# SWD.net
KiCad netlist of a schematic drawn in EAGLE
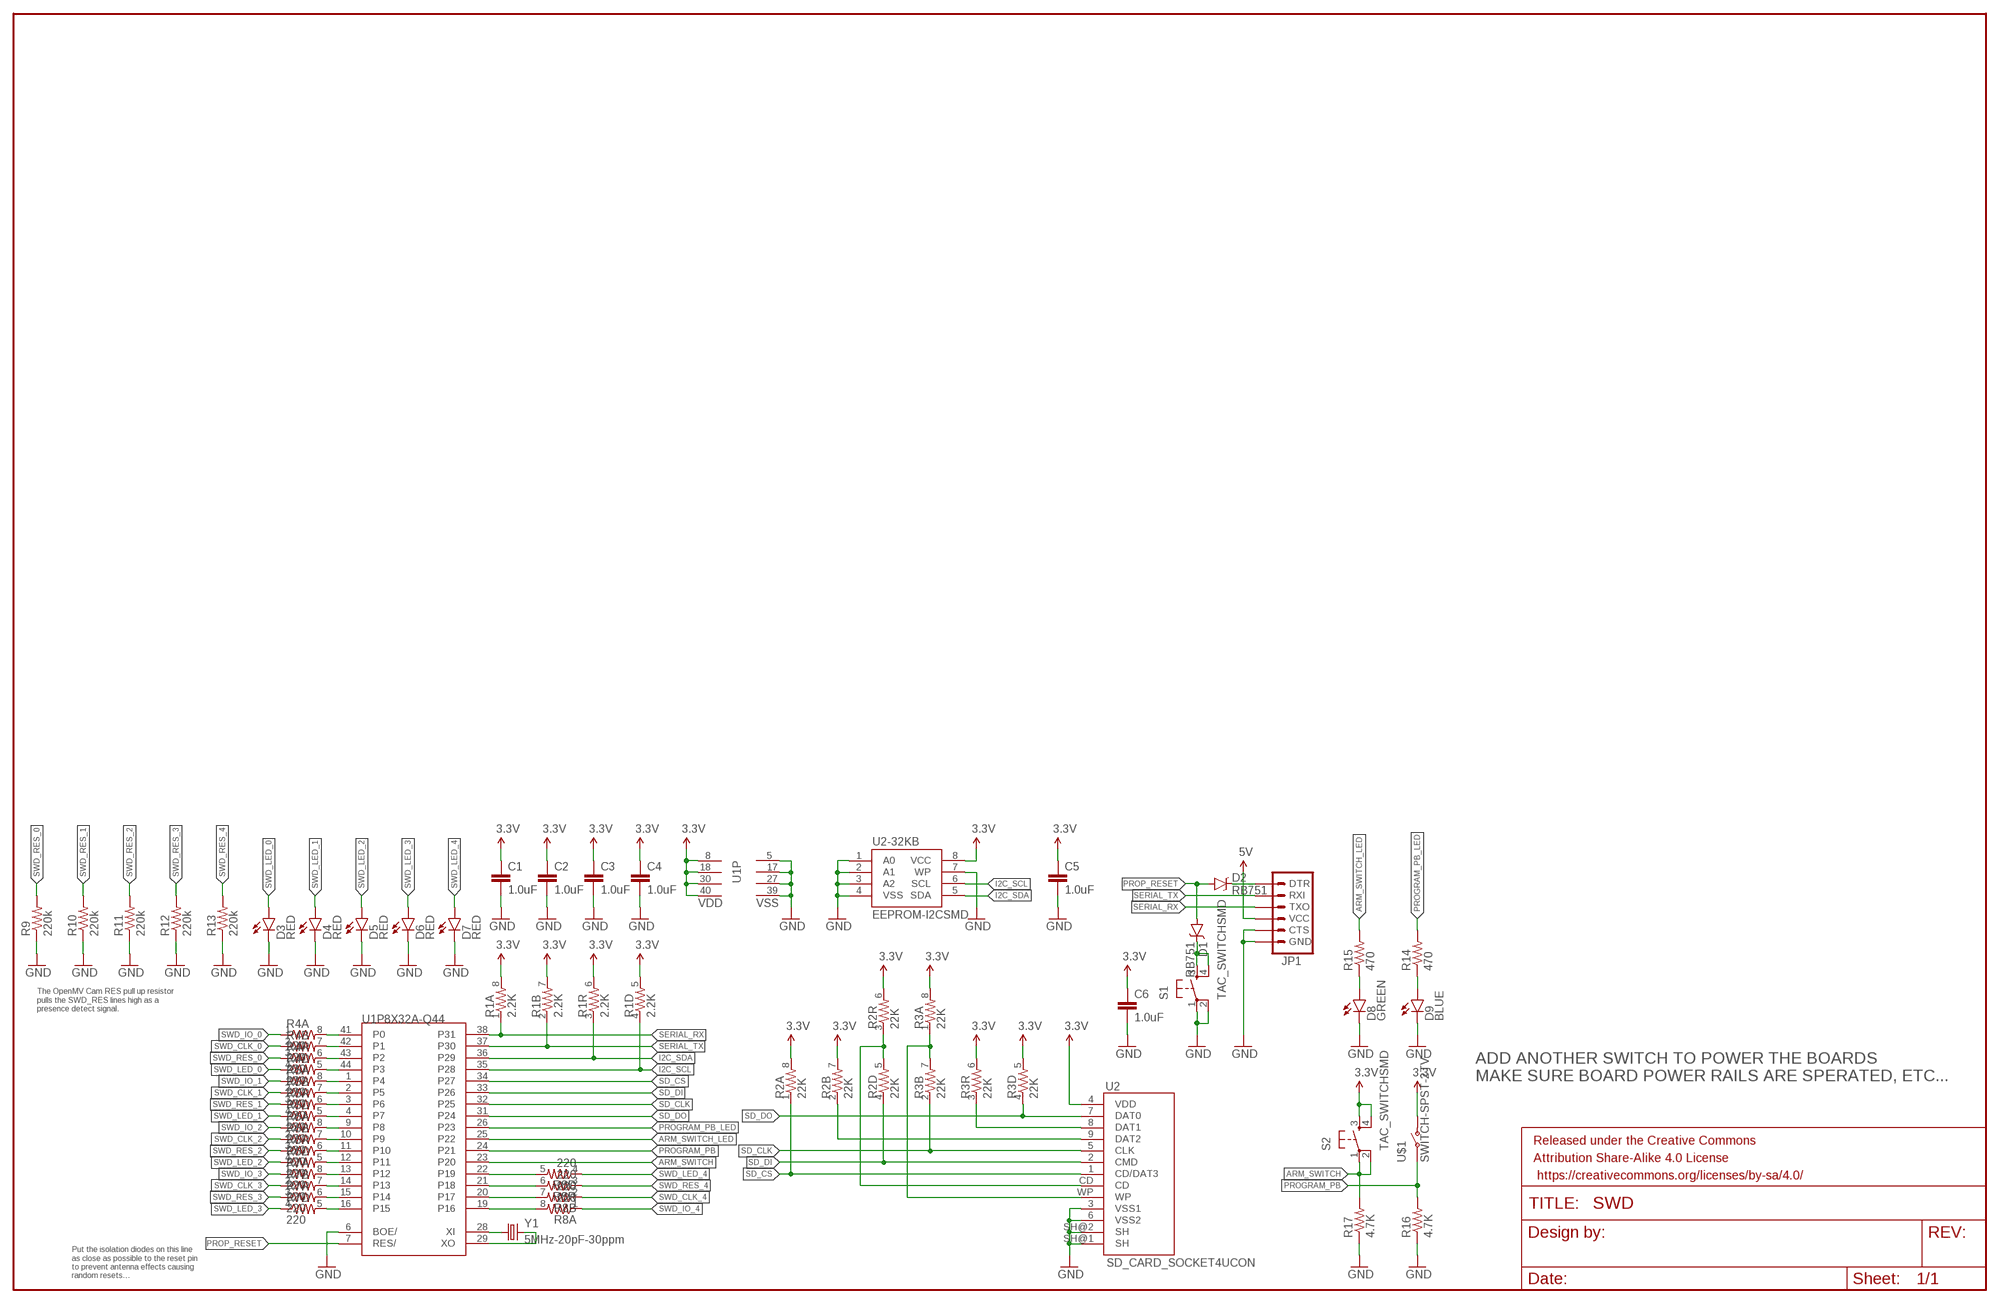
[diagram p0: schematic, sheet 1]

(export (version "E")
  (design (tool "Eeschema 10.0.6"))
  (components
    (comp (ref "C1")
      (value "1.0uF")
      (footprint "eagle-import:0402-CAP")
      (libsource (lib "eagle-import") (part "1.0UF-16V-10%(0402)"))
    )
    (comp (ref "C2")
      (value "1.0uF")
      (footprint "eagle-import:0402-CAP")
      (libsource (lib "eagle-import") (part "1.0UF-16V-10%(0402)"))
    )
    (comp (ref "C3")
      (value "1.0uF")
      (footprint "eagle-import:0402-CAP")
      (libsource (lib "eagle-import") (part "1.0UF-16V-10%(0402)"))
    )
    (comp (ref "C4")
      (value "1.0uF")
      (footprint "eagle-import:0402-CAP")
      (libsource (lib "eagle-import") (part "1.0UF-16V-10%(0402)"))
    )
    (comp (ref "C5")
      (value "1.0uF")
      (footprint "eagle-import:0402-CAP")
      (libsource (lib "eagle-import") (part "1.0UF-16V-10%(0402)"))
    )
    (comp (ref "C6")
      (value "1.0uF")
      (footprint "eagle-import:0402-CAP")
      (libsource (lib "eagle-import") (part "1.0UF-16V-10%(0402)"))
    )
    (comp (ref "D1")
      (value "RB751")
      (footprint "eagle-import:SOD-523")
      (libsource (lib "eagle-import") (part "RB751"))
    )
    (comp (ref "D2")
      (value "RB751")
      (footprint "eagle-import:SOD-523")
      (libsource (lib "eagle-import") (part "RB751"))
    )
    (comp (ref "D3")
      (value "RED")
      (footprint "eagle-import:LED-0603")
      (libsource (lib "eagle-import") (part "LED-RED0603"))
    )
    (comp (ref "D4")
      (value "RED")
      (footprint "eagle-import:LED-0603")
      (libsource (lib "eagle-import") (part "LED-RED0603"))
    )
    (comp (ref "D5")
      (value "RED")
      (footprint "eagle-import:LED-0603")
      (libsource (lib "eagle-import") (part "LED-RED0603"))
    )
    (comp (ref "D6")
      (value "RED")
      (footprint "eagle-import:LED-0603")
      (libsource (lib "eagle-import") (part "LED-RED0603"))
    )
    (comp (ref "D7")
      (value "RED")
      (footprint "eagle-import:LED-0603")
      (libsource (lib "eagle-import") (part "LED-RED0603"))
    )
    (comp (ref "D8")
      (value "GREEN")
      (footprint "eagle-import:LED-0603")
      (libsource (lib "eagle-import") (part "LED-GREEN0603"))
    )
    (comp (ref "D9")
      (value "BLUE")
      (footprint "eagle-import:LED-0603")
      (libsource (lib "eagle-import") (part "LED-BLUE0603"))
    )
    (comp (ref "FRAME1")
      (value "FRAME-LEDGER")
      (footprint "eagle-import:CREATIVE_COMMONS")
      (libsource (lib "eagle-import") (part "FRAME-LEDGER"))
    )
    (comp (ref "JP1")
      (value "ARDUINO_SERIAL_PROGRAMPTH")
      (footprint "eagle-import:1X06")
      (libsource (lib "eagle-import") (part "ARDUINO_SERIAL_PROGRAMPTH"))
    )
    (comp (ref "R1")
      (value "2.2K")
      (footprint "eagle-import:0603-ARV")
      (libsource (lib "eagle-import") (part "RESISTOR-ARRAY0603-ARV"))
    )
    (comp (ref "R2")
      (value "22K")
      (footprint "eagle-import:0603-ARV")
      (libsource (lib "eagle-import") (part "RESISTOR-ARRAY0603-ARV"))
    )
    (comp (ref "R3")
      (value "22K")
      (footprint "eagle-import:0603-ARV")
      (libsource (lib "eagle-import") (part "RESISTOR-ARRAY0603-ARV"))
    )
    (comp (ref "R4")
      (value "220")
      (footprint "eagle-import:0603-ARV")
      (libsource (lib "eagle-import") (part "RESISTOR-ARRAY0603-ARV"))
    )
    (comp (ref "R5")
      (value "220")
      (footprint "eagle-import:0603-ARV")
      (libsource (lib "eagle-import") (part "RESISTOR-ARRAY0603-ARV"))
    )
    (comp (ref "R6")
      (value "220")
      (footprint "eagle-import:0603-ARV")
      (libsource (lib "eagle-import") (part "RESISTOR-ARRAY0603-ARV"))
    )
    (comp (ref "R7")
      (value "220")
      (footprint "eagle-import:0603-ARV")
      (libsource (lib "eagle-import") (part "RESISTOR-ARRAY0603-ARV"))
    )
    (comp (ref "R8")
      (value "220")
      (footprint "eagle-import:0603-ARV")
      (libsource (lib "eagle-import") (part "RESISTOR-ARRAY0603-ARV"))
    )
    (comp (ref "R9")
      (value "220k")
      (footprint "eagle-import:0603-RES")
      (libsource (lib "eagle-import") (part "220KOHM1/10W1%(0603)"))
    )
    (comp (ref "R10")
      (value "220k")
      (footprint "eagle-import:0603-RES")
      (libsource (lib "eagle-import") (part "220KOHM1/10W1%(0603)"))
    )
    (comp (ref "R11")
      (value "220k")
      (footprint "eagle-import:0603-RES")
      (libsource (lib "eagle-import") (part "220KOHM1/10W1%(0603)"))
    )
    (comp (ref "R12")
      (value "220k")
      (footprint "eagle-import:0603-RES")
      (libsource (lib "eagle-import") (part "220KOHM1/10W1%(0603)"))
    )
    (comp (ref "R13")
      (value "220k")
      (footprint "eagle-import:0603-RES")
      (libsource (lib "eagle-import") (part "220KOHM1/10W1%(0603)"))
    )
    (comp (ref "R14")
      (value "470")
      (footprint "eagle-import:0603-RES")
      (libsource (lib "eagle-import") (part "470OHM1/10W1%(0603)"))
    )
    (comp (ref "R15")
      (value "470")
      (footprint "eagle-import:0603-RES")
      (libsource (lib "eagle-import") (part "470OHM1/10W1%(0603)"))
    )
    (comp (ref "R16")
      (value "4.7K")
      (footprint "eagle-import:0603-RES")
      (libsource (lib "eagle-import") (part "4.7KOHM-1/10W-1%(0603)"))
    )
    (comp (ref "R17")
      (value "4.7K")
      (footprint "eagle-import:0603-RES")
      (libsource (lib "eagle-import") (part "4.7KOHM-1/10W-1%(0603)"))
    )
    (comp (ref "S1")
      (value "TAC_SWITCHSMD")
      (footprint "eagle-import:TACTILE-SWITCH-SMD")
      (libsource (lib "eagle-import") (part "TAC_SWITCHSMD"))
    )
    (comp (ref "S2")
      (value "TAC_SWITCHSMD")
      (footprint "eagle-import:TACTILE-SWITCH-SMD")
      (libsource (lib "eagle-import") (part "TAC_SWITCHSMD"))
    )
    (comp (ref "U$1")
      (value "SWITCH-SPST-2TV")
      (footprint "eagle-import:SWITCH-SPST-VERTICAL")
      (libsource (lib "eagle-import") (part "SWITCH-SPST-2TV"))
    )
    (comp (ref "U1")
      (value "P8X32A-Q44")
      (footprint "eagle-import:P8X32A-Q44")
      (libsource (lib "eagle-import") (part "P8X32A-Q44"))
    )
    (comp (ref "U2")
      (value "SD_CARD_SOCKET4UCON")
      (footprint "eagle-import:SDCARD_4UCONN")
      (libsource (lib "eagle-import") (part "SD_CARD_SOCKET4UCON"))
    )
    (comp (ref "U2-32KB")
      (value "EEPROM-I2CSMD")
      (footprint "eagle-import:SO08")
      (libsource (lib "eagle-import") (part "EEPROM-I2CSMD"))
    )
    (comp (ref "Y1")
      (value "5MHz-20pF-30ppm")
      (footprint "eagle-import:HC49UP")
      (libsource (lib "eagle-import") (part "CRYSTALSMD"))
    )
  )
  (nets
    (net (code "1") (name "3.3V") (class "Default")
      (node (ref "C1") (pin "1") (pinfunction "1_1") (pintype "passive"))
      (node (ref "C2") (pin "1") (pinfunction "1_1") (pintype "passive"))
      (node (ref "C3") (pin "1") (pinfunction "1_1") (pintype "passive"))
      (node (ref "C4") (pin "1") (pinfunction "1_1") (pintype "passive"))
      (node (ref "C5") (pin "1") (pinfunction "1_1") (pintype "passive"))
      (node (ref "C6") (pin "1") (pinfunction "1_1") (pintype "passive"))
      (node (ref "R1") (pin "5") (pinfunction "2_5") (pintype "passive"))
      (node (ref "R1") (pin "6") (pinfunction "2_6") (pintype "passive"))
      (node (ref "R1") (pin "7") (pinfunction "2_7") (pintype "passive"))
      (node (ref "R1") (pin "8") (pinfunction "2_8") (pintype "passive"))
      (node (ref "R2") (pin "6") (pinfunction "2_6") (pintype "passive"))
      (node (ref "R2") (pin "7") (pinfunction "2_7") (pintype "passive"))
      (node (ref "R2") (pin "8") (pinfunction "2_8") (pintype "passive"))
      (node (ref "R3") (pin "5") (pinfunction "2_5") (pintype "passive"))
      (node (ref "R3") (pin "6") (pinfunction "2_6") (pintype "passive"))
      (node (ref "R3") (pin "8") (pinfunction "2_8") (pintype "passive"))
      (node (ref "S2") (pin "3") (pinfunction "3_3") (pintype "passive"))
      (node (ref "S2") (pin "4") (pinfunction "4_4") (pintype "passive"))
      (node (ref "U$1") (pin "1") (pinfunction "O_1") (pintype "passive"))
      (node (ref "U1") (pin "18") (pinfunction "VDD_18") (pintype "power_in"))
      (node (ref "U1") (pin "30") (pinfunction "VDD_30") (pintype "power_in"))
      (node (ref "U1") (pin "40") (pinfunction "VDD_40") (pintype "power_in"))
      (node (ref "U1") (pin "8") (pinfunction "VDD_8") (pintype "power_in"))
      (node (ref "U2") (pin "4") (pinfunction "VDD_4") (pintype "power_in"))
      (node (ref "U2-32KB") (pin "8") (pinfunction "VCC_8") (pintype "power_in"))
    )
    (net (code "2") (name "5V") (class "Default")
      (node (ref "JP1") (pin "4") (pinfunction "VCC_4") (pintype "passive"))
    )
    (net (code "3") (name "ARM_SWITCH") (class "Default")
      (node (ref "R17") (pin "2") (pinfunction "2_2") (pintype "passive"))
      (node (ref "S2") (pin "1") (pinfunction "1_1") (pintype "passive"))
      (node (ref "S2") (pin "2") (pinfunction "2_2") (pintype "passive"))
      (node (ref "U1") (pin "23") (pinfunction "P20_23") (pintype "bidirectional"))
    )
    (net (code "4") (name "ARM_SWITCH_LED") (class "Default")
      (node (ref "R15") (pin "2") (pinfunction "2_2") (pintype "passive"))
      (node (ref "U1") (pin "25") (pinfunction "P22_25") (pintype "bidirectional"))
    )
    (net (code "5") (name "GND") (class "Default")
      (node (ref "C1") (pin "2") (pinfunction "2_2") (pintype "passive"))
      (node (ref "C2") (pin "2") (pinfunction "2_2") (pintype "passive"))
      (node (ref "C3") (pin "2") (pinfunction "2_2") (pintype "passive"))
      (node (ref "C4") (pin "2") (pinfunction "2_2") (pintype "passive"))
      (node (ref "C5") (pin "2") (pinfunction "2_2") (pintype "passive"))
      (node (ref "C6") (pin "2") (pinfunction "2_2") (pintype "passive"))
      (node (ref "D3") (pin "C") (pinfunction "C_C") (pintype "passive"))
      (node (ref "D4") (pin "C") (pinfunction "C_C") (pintype "passive"))
      (node (ref "D5") (pin "C") (pinfunction "C_C") (pintype "passive"))
      (node (ref "D6") (pin "C") (pinfunction "C_C") (pintype "passive"))
      (node (ref "D7") (pin "C") (pinfunction "C_C") (pintype "passive"))
      (node (ref "D8") (pin "C") (pinfunction "C_C") (pintype "passive"))
      (node (ref "D9") (pin "C") (pinfunction "C_C") (pintype "passive"))
      (node (ref "JP1") (pin "5") (pinfunction "CTS_5") (pintype "passive"))
      (node (ref "JP1") (pin "6") (pinfunction "GND_6") (pintype "passive"))
      (node (ref "R10") (pin "1") (pinfunction "1_1") (pintype "passive"))
      (node (ref "R11") (pin "1") (pinfunction "1_1") (pintype "passive"))
      (node (ref "R12") (pin "1") (pinfunction "1_1") (pintype "passive"))
      (node (ref "R13") (pin "1") (pinfunction "1_1") (pintype "passive"))
      (node (ref "R16") (pin "1") (pinfunction "1_1") (pintype "passive"))
      (node (ref "R17") (pin "1") (pinfunction "1_1") (pintype "passive"))
      (node (ref "R9") (pin "1") (pinfunction "1_1") (pintype "passive"))
      (node (ref "S1") (pin "1") (pinfunction "1_1") (pintype "passive"))
      (node (ref "S1") (pin "2") (pinfunction "2_2") (pintype "passive"))
      (node (ref "U1") (pin "17") (pinfunction "VSS_17") (pintype "power_in"))
      (node (ref "U1") (pin "27") (pinfunction "VSS_27") (pintype "power_in"))
      (node (ref "U1") (pin "39") (pinfunction "VSS_39") (pintype "power_in"))
      (node (ref "U1") (pin "5") (pinfunction "VSS_5") (pintype "power_in"))
      (node (ref "U1") (pin "6") (pinfunction "BOE/_6") (pintype "input"))
      (node (ref "U2") (pin "3") (pinfunction "VSS1_3") (pintype "power_in"))
      (node (ref "U2") (pin "6") (pinfunction "VSS2_6") (pintype "power_in"))
      (node (ref "U2") (pin "SH@1") (pinfunction "SH_SH@1") (pintype "bidirectional"))
      (node (ref "U2") (pin "SH@2") (pinfunction "SH_SH@2") (pintype "bidirectional"))
      (node (ref "U2-32KB") (pin "1") (pinfunction "A0_1") (pintype "bidirectional"))
      (node (ref "U2-32KB") (pin "2") (pinfunction "A1_2") (pintype "bidirectional"))
      (node (ref "U2-32KB") (pin "3") (pinfunction "A2_3") (pintype "bidirectional"))
      (node (ref "U2-32KB") (pin "4") (pinfunction "VSS_4") (pintype "power_in"))
      (node (ref "U2-32KB") (pin "7") (pinfunction "WP_7") (pintype "bidirectional"))
    )
    (net (code "6") (name "I2C_SCL") (class "Default")
      (node (ref "R1") (pin "4") (pinfunction "1_4") (pintype "passive"))
      (node (ref "U1") (pin "35") (pinfunction "P28_35") (pintype "bidirectional"))
      (node (ref "U2-32KB") (pin "6") (pinfunction "SCL_6") (pintype "bidirectional"))
    )
    (net (code "7") (name "I2C_SDA") (class "Default")
      (node (ref "R1") (pin "3") (pinfunction "1_3") (pintype "passive"))
      (node (ref "U1") (pin "36") (pinfunction "P29_36") (pintype "bidirectional"))
      (node (ref "U2-32KB") (pin "5") (pinfunction "SDA_5") (pintype "bidirectional"))
    )
    (net (code "8") (name "Net-(D1-PadC)") (class "Default")
      (node (ref "D1") (pin "C") (pinfunction "C_C") (pintype "passive"))
      (node (ref "S1") (pin "3") (pinfunction "3_3") (pintype "passive"))
      (node (ref "S1") (pin "4") (pinfunction "4_4") (pintype "passive"))
    )
    (net (code "9") (name "Net-(D8-PadA)") (class "Default")
      (node (ref "D8") (pin "A") (pinfunction "A_A") (pintype "passive"))
      (node (ref "R15") (pin "1") (pinfunction "1_1") (pintype "passive"))
    )
    (net (code "10") (name "Net-(D9-PadA)") (class "Default")
      (node (ref "D9") (pin "A") (pinfunction "A_A") (pintype "passive"))
      (node (ref "R14") (pin "1") (pinfunction "1_1") (pintype "passive"))
    )
    (net (code "11") (name "Net-(JP1-DTR)") (class "Default")
      (node (ref "D2") (pin "C") (pinfunction "C_C") (pintype "passive"))
      (node (ref "JP1") (pin "1") (pinfunction "DTR_1") (pintype "passive"))
    )
    (net (code "12") (name "Net-(R2C-2)") (class "Default")
      (node (ref "R2") (pin "3") (pinfunction "1_3") (pintype "passive"))
      (node (ref "R2") (pin "5") (pinfunction "2_5") (pintype "passive"))
      (node (ref "U2") (pin "CD") (pinfunction "CD_CD") (pintype "bidirectional"))
    )
    (net (code "13") (name "Net-(R3B-2)") (class "Default")
      (node (ref "R3") (pin "1") (pinfunction "1_1") (pintype "passive"))
      (node (ref "R3") (pin "7") (pinfunction "2_7") (pintype "passive"))
      (node (ref "U2") (pin "WP") (pinfunction "WP_WP") (pintype "bidirectional"))
    )
    (net (code "14") (name "Net-(R4A-2)") (class "Default")
      (node (ref "R4") (pin "8") (pinfunction "2_8") (pintype "passive"))
      (node (ref "U1") (pin "41") (pinfunction "P0_41") (pintype "bidirectional"))
    )
    (net (code "15") (name "Net-(R4B-2)") (class "Default")
      (node (ref "R4") (pin "7") (pinfunction "2_7") (pintype "passive"))
      (node (ref "U1") (pin "42") (pinfunction "P1_42") (pintype "bidirectional"))
    )
    (net (code "16") (name "Net-(R4C-2)") (class "Default")
      (node (ref "R4") (pin "5") (pinfunction "2_5") (pintype "passive"))
      (node (ref "U1") (pin "44") (pinfunction "P3_44") (pintype "bidirectional"))
    )
    (net (code "17") (name "Net-(R4D-2)") (class "Default")
      (node (ref "R4") (pin "6") (pinfunction "2_6") (pintype "passive"))
      (node (ref "U1") (pin "43") (pinfunction "P2_43") (pintype "bidirectional"))
    )
    (net (code "18") (name "Net-(R5A-2)") (class "Default")
      (node (ref "R5") (pin "8") (pinfunction "2_8") (pintype "passive"))
      (node (ref "U1") (pin "1") (pinfunction "P4_1") (pintype "bidirectional"))
    )
    (net (code "19") (name "Net-(R5B-2)") (class "Default")
      (node (ref "R5") (pin "7") (pinfunction "2_7") (pintype "passive"))
      (node (ref "U1") (pin "2") (pinfunction "P5_2") (pintype "bidirectional"))
    )
    (net (code "20") (name "Net-(R5C-2)") (class "Default")
      (node (ref "R5") (pin "5") (pinfunction "2_5") (pintype "passive"))
      (node (ref "U1") (pin "4") (pinfunction "P7_4") (pintype "bidirectional"))
    )
    (net (code "21") (name "Net-(R5D-2)") (class "Default")
      (node (ref "R5") (pin "6") (pinfunction "2_6") (pintype "passive"))
      (node (ref "U1") (pin "3") (pinfunction "P6_3") (pintype "bidirectional"))
    )
    (net (code "22") (name "Net-(R6A-2)") (class "Default")
      (node (ref "R6") (pin "8") (pinfunction "2_8") (pintype "passive"))
      (node (ref "U1") (pin "9") (pinfunction "P8_9") (pintype "bidirectional"))
    )
    (net (code "23") (name "Net-(R6B-2)") (class "Default")
      (node (ref "R6") (pin "7") (pinfunction "2_7") (pintype "passive"))
      (node (ref "U1") (pin "10") (pinfunction "P9_10") (pintype "bidirectional"))
    )
    (net (code "24") (name "Net-(R6C-2)") (class "Default")
      (node (ref "R6") (pin "5") (pinfunction "2_5") (pintype "passive"))
      (node (ref "U1") (pin "12") (pinfunction "P11_12") (pintype "bidirectional"))
    )
    (net (code "25") (name "Net-(R6D-2)") (class "Default")
      (node (ref "R6") (pin "6") (pinfunction "2_6") (pintype "passive"))
      (node (ref "U1") (pin "11") (pinfunction "P10_11") (pintype "bidirectional"))
    )
    (net (code "26") (name "Net-(R7A-2)") (class "Default")
      (node (ref "R7") (pin "8") (pinfunction "2_8") (pintype "passive"))
      (node (ref "U1") (pin "13") (pinfunction "P12_13") (pintype "bidirectional"))
    )
    (net (code "27") (name "Net-(R7B-2)") (class "Default")
      (node (ref "R7") (pin "7") (pinfunction "2_7") (pintype "passive"))
      (node (ref "U1") (pin "14") (pinfunction "P13_14") (pintype "bidirectional"))
    )
    (net (code "28") (name "Net-(R7C-2)") (class "Default")
      (node (ref "R7") (pin "5") (pinfunction "2_5") (pintype "passive"))
      (node (ref "U1") (pin "16") (pinfunction "P15_16") (pintype "bidirectional"))
    )
    (net (code "29") (name "Net-(R7D-2)") (class "Default")
      (node (ref "R7") (pin "6") (pinfunction "2_6") (pintype "passive"))
      (node (ref "U1") (pin "15") (pinfunction "P14_15") (pintype "bidirectional"))
    )
    (net (code "30") (name "Net-(R8A-2)") (class "Default")
      (node (ref "R8") (pin "8") (pinfunction "2_8") (pintype "passive"))
      (node (ref "U1") (pin "19") (pinfunction "P16_19") (pintype "bidirectional"))
    )
    (net (code "31") (name "Net-(R8B-2)") (class "Default")
      (node (ref "R8") (pin "7") (pinfunction "2_7") (pintype "passive"))
      (node (ref "U1") (pin "20") (pinfunction "P17_20") (pintype "bidirectional"))
    )
    (net (code "32") (name "Net-(R8C-2)") (class "Default")
      (node (ref "R8") (pin "5") (pinfunction "2_5") (pintype "passive"))
      (node (ref "U1") (pin "22") (pinfunction "P19_22") (pintype "bidirectional"))
    )
    (net (code "33") (name "Net-(R8D-2)") (class "Default")
      (node (ref "R8") (pin "6") (pinfunction "2_6") (pintype "passive"))
      (node (ref "U1") (pin "21") (pinfunction "P18_21") (pintype "bidirectional"))
    )
    (net (code "34") (name "Net-(U1B-XI)") (class "Default")
      (node (ref "U1") (pin "28") (pinfunction "XI_28") (pintype "input"))
      (node (ref "Y1") (pin "1") (pinfunction "1_1") (pintype "passive"))
    )
    (net (code "35") (name "Net-(U1B-XO)") (class "Default")
      (node (ref "U1") (pin "29") (pinfunction "XO_29") (pintype "output"))
      (node (ref "Y1") (pin "2") (pinfunction "2_2") (pintype "passive"))
    )
    (net (code "36") (name "PROGRAM_PB") (class "Default")
      (node (ref "R16") (pin "2") (pinfunction "2_2") (pintype "passive"))
      (node (ref "U$1") (pin "2") (pinfunction "P_2") (pintype "passive"))
      (node (ref "U1") (pin "24") (pinfunction "P21_24") (pintype "bidirectional"))
    )
    (net (code "37") (name "PROGRAM_PB_LED") (class "Default")
      (node (ref "R14") (pin "2") (pinfunction "2_2") (pintype "passive"))
      (node (ref "U1") (pin "26") (pinfunction "P23_26") (pintype "bidirectional"))
    )
    (net (code "38") (name "PROP_RESET") (class "Default")
      (node (ref "D1") (pin "A") (pinfunction "A_A") (pintype "passive"))
      (node (ref "D2") (pin "A") (pinfunction "A_A") (pintype "passive"))
      (node (ref "U1") (pin "7") (pinfunction "RES/_7") (pintype "bidirectional"))
    )
    (net (code "39") (name "SD_CLK") (class "Default")
      (node (ref "R3") (pin "2") (pinfunction "1_2") (pintype "passive"))
      (node (ref "U1") (pin "32") (pinfunction "P25_32") (pintype "bidirectional"))
      (node (ref "U2") (pin "5") (pinfunction "CLK_5") (pintype "bidirectional"))
    )
    (net (code "40") (name "SD_CS") (class "Default")
      (node (ref "R2") (pin "1") (pinfunction "1_1") (pintype "passive"))
      (node (ref "R3") (pin "3") (pinfunction "1_3") (pintype "passive"))
      (node (ref "U1") (pin "34") (pinfunction "P27_34") (pintype "bidirectional"))
      (node (ref "U2") (pin "1") (pinfunction "CD/DAT3_1") (pintype "bidirectional"))
      (node (ref "U2") (pin "8") (pinfunction "DAT1_8") (pintype "bidirectional"))
    )
    (net (code "41") (name "SD_DI") (class "Default")
      (node (ref "R2") (pin "4") (pinfunction "1_4") (pintype "passive"))
      (node (ref "U1") (pin "33") (pinfunction "P26_33") (pintype "bidirectional"))
      (node (ref "U2") (pin "2") (pinfunction "CMD_2") (pintype "bidirectional"))
    )
    (net (code "42") (name "SD_DO") (class "Default")
      (node (ref "R2") (pin "2") (pinfunction "1_2") (pintype "passive"))
      (node (ref "R3") (pin "4") (pinfunction "1_4") (pintype "passive"))
      (node (ref "U1") (pin "31") (pinfunction "P24_31") (pintype "bidirectional"))
      (node (ref "U2") (pin "7") (pinfunction "DAT0_7") (pintype "bidirectional"))
      (node (ref "U2") (pin "9") (pinfunction "DAT2_9") (pintype "bidirectional"))
    )
    (net (code "43") (name "SERIAL_RX") (class "Default")
      (node (ref "JP1") (pin "3") (pinfunction "TXO_3") (pintype "passive"))
      (node (ref "R1") (pin "1") (pinfunction "1_1") (pintype "passive"))
      (node (ref "U1") (pin "38") (pinfunction "P31_38") (pintype "bidirectional"))
    )
    (net (code "44") (name "SERIAL_TX") (class "Default")
      (node (ref "JP1") (pin "2") (pinfunction "RXI_2") (pintype "passive"))
      (node (ref "R1") (pin "2") (pinfunction "1_2") (pintype "passive"))
      (node (ref "U1") (pin "37") (pinfunction "P30_37") (pintype "bidirectional"))
    )
    (net (code "45") (name "SWD_CLK_0") (class "Default")
      (node (ref "R4") (pin "2") (pinfunction "1_2") (pintype "passive"))
    )
    (net (code "46") (name "SWD_CLK_1") (class "Default")
      (node (ref "R5") (pin "2") (pinfunction "1_2") (pintype "passive"))
    )
    (net (code "47") (name "SWD_CLK_2") (class "Default")
      (node (ref "R6") (pin "2") (pinfunction "1_2") (pintype "passive"))
    )
    (net (code "48") (name "SWD_CLK_3") (class "Default")
      (node (ref "R7") (pin "2") (pinfunction "1_2") (pintype "passive"))
    )
    (net (code "49") (name "SWD_CLK_4") (class "Default")
      (node (ref "R8") (pin "2") (pinfunction "1_2") (pintype "passive"))
    )
    (net (code "50") (name "SWD_IO_0") (class "Default")
      (node (ref "R4") (pin "1") (pinfunction "1_1") (pintype "passive"))
    )
    (net (code "51") (name "SWD_IO_1") (class "Default")
      (node (ref "R5") (pin "1") (pinfunction "1_1") (pintype "passive"))
    )
    (net (code "52") (name "SWD_IO_2") (class "Default")
      (node (ref "R6") (pin "1") (pinfunction "1_1") (pintype "passive"))
    )
    (net (code "53") (name "SWD_IO_3") (class "Default")
      (node (ref "R7") (pin "1") (pinfunction "1_1") (pintype "passive"))
    )
    (net (code "54") (name "SWD_IO_4") (class "Default")
      (node (ref "R8") (pin "1") (pinfunction "1_1") (pintype "passive"))
    )
    (net (code "55") (name "SWD_LED_0") (class "Default")
      (node (ref "D3") (pin "A") (pinfunction "A_A") (pintype "passive"))
      (node (ref "R4") (pin "4") (pinfunction "1_4") (pintype "passive"))
    )
    (net (code "56") (name "SWD_LED_1") (class "Default")
      (node (ref "D4") (pin "A") (pinfunction "A_A") (pintype "passive"))
      (node (ref "R5") (pin "4") (pinfunction "1_4") (pintype "passive"))
    )
    (net (code "57") (name "SWD_LED_2") (class "Default")
      (node (ref "D5") (pin "A") (pinfunction "A_A") (pintype "passive"))
      (node (ref "R6") (pin "4") (pinfunction "1_4") (pintype "passive"))
    )
    (net (code "58") (name "SWD_LED_3") (class "Default")
      (node (ref "D6") (pin "A") (pinfunction "A_A") (pintype "passive"))
      (node (ref "R7") (pin "4") (pinfunction "1_4") (pintype "passive"))
    )
    (net (code "59") (name "SWD_LED_4") (class "Default")
      (node (ref "D7") (pin "A") (pinfunction "A_A") (pintype "passive"))
      (node (ref "R8") (pin "4") (pinfunction "1_4") (pintype "passive"))
    )
    (net (code "60") (name "SWD_RES_0") (class "Default")
      (node (ref "R4") (pin "3") (pinfunction "1_3") (pintype "passive"))
      (node (ref "R9") (pin "2") (pinfunction "2_2") (pintype "passive"))
    )
    (net (code "61") (name "SWD_RES_1") (class "Default")
      (node (ref "R10") (pin "2") (pinfunction "2_2") (pintype "passive"))
      (node (ref "R5") (pin "3") (pinfunction "1_3") (pintype "passive"))
    )
    (net (code "62") (name "SWD_RES_2") (class "Default")
      (node (ref "R11") (pin "2") (pinfunction "2_2") (pintype "passive"))
      (node (ref "R6") (pin "3") (pinfunction "1_3") (pintype "passive"))
    )
    (net (code "63") (name "SWD_RES_3") (class "Default")
      (node (ref "R12") (pin "2") (pinfunction "2_2") (pintype "passive"))
      (node (ref "R7") (pin "3") (pinfunction "1_3") (pintype "passive"))
    )
    (net (code "64") (name "SWD_RES_4") (class "Default")
      (node (ref "R13") (pin "2") (pinfunction "2_2") (pintype "passive"))
      (node (ref "R8") (pin "3") (pinfunction "1_3") (pintype "passive"))
    )
  )
)
